# Sheet1.net
KiCad netlist of a schematic drawn in Altium Designer
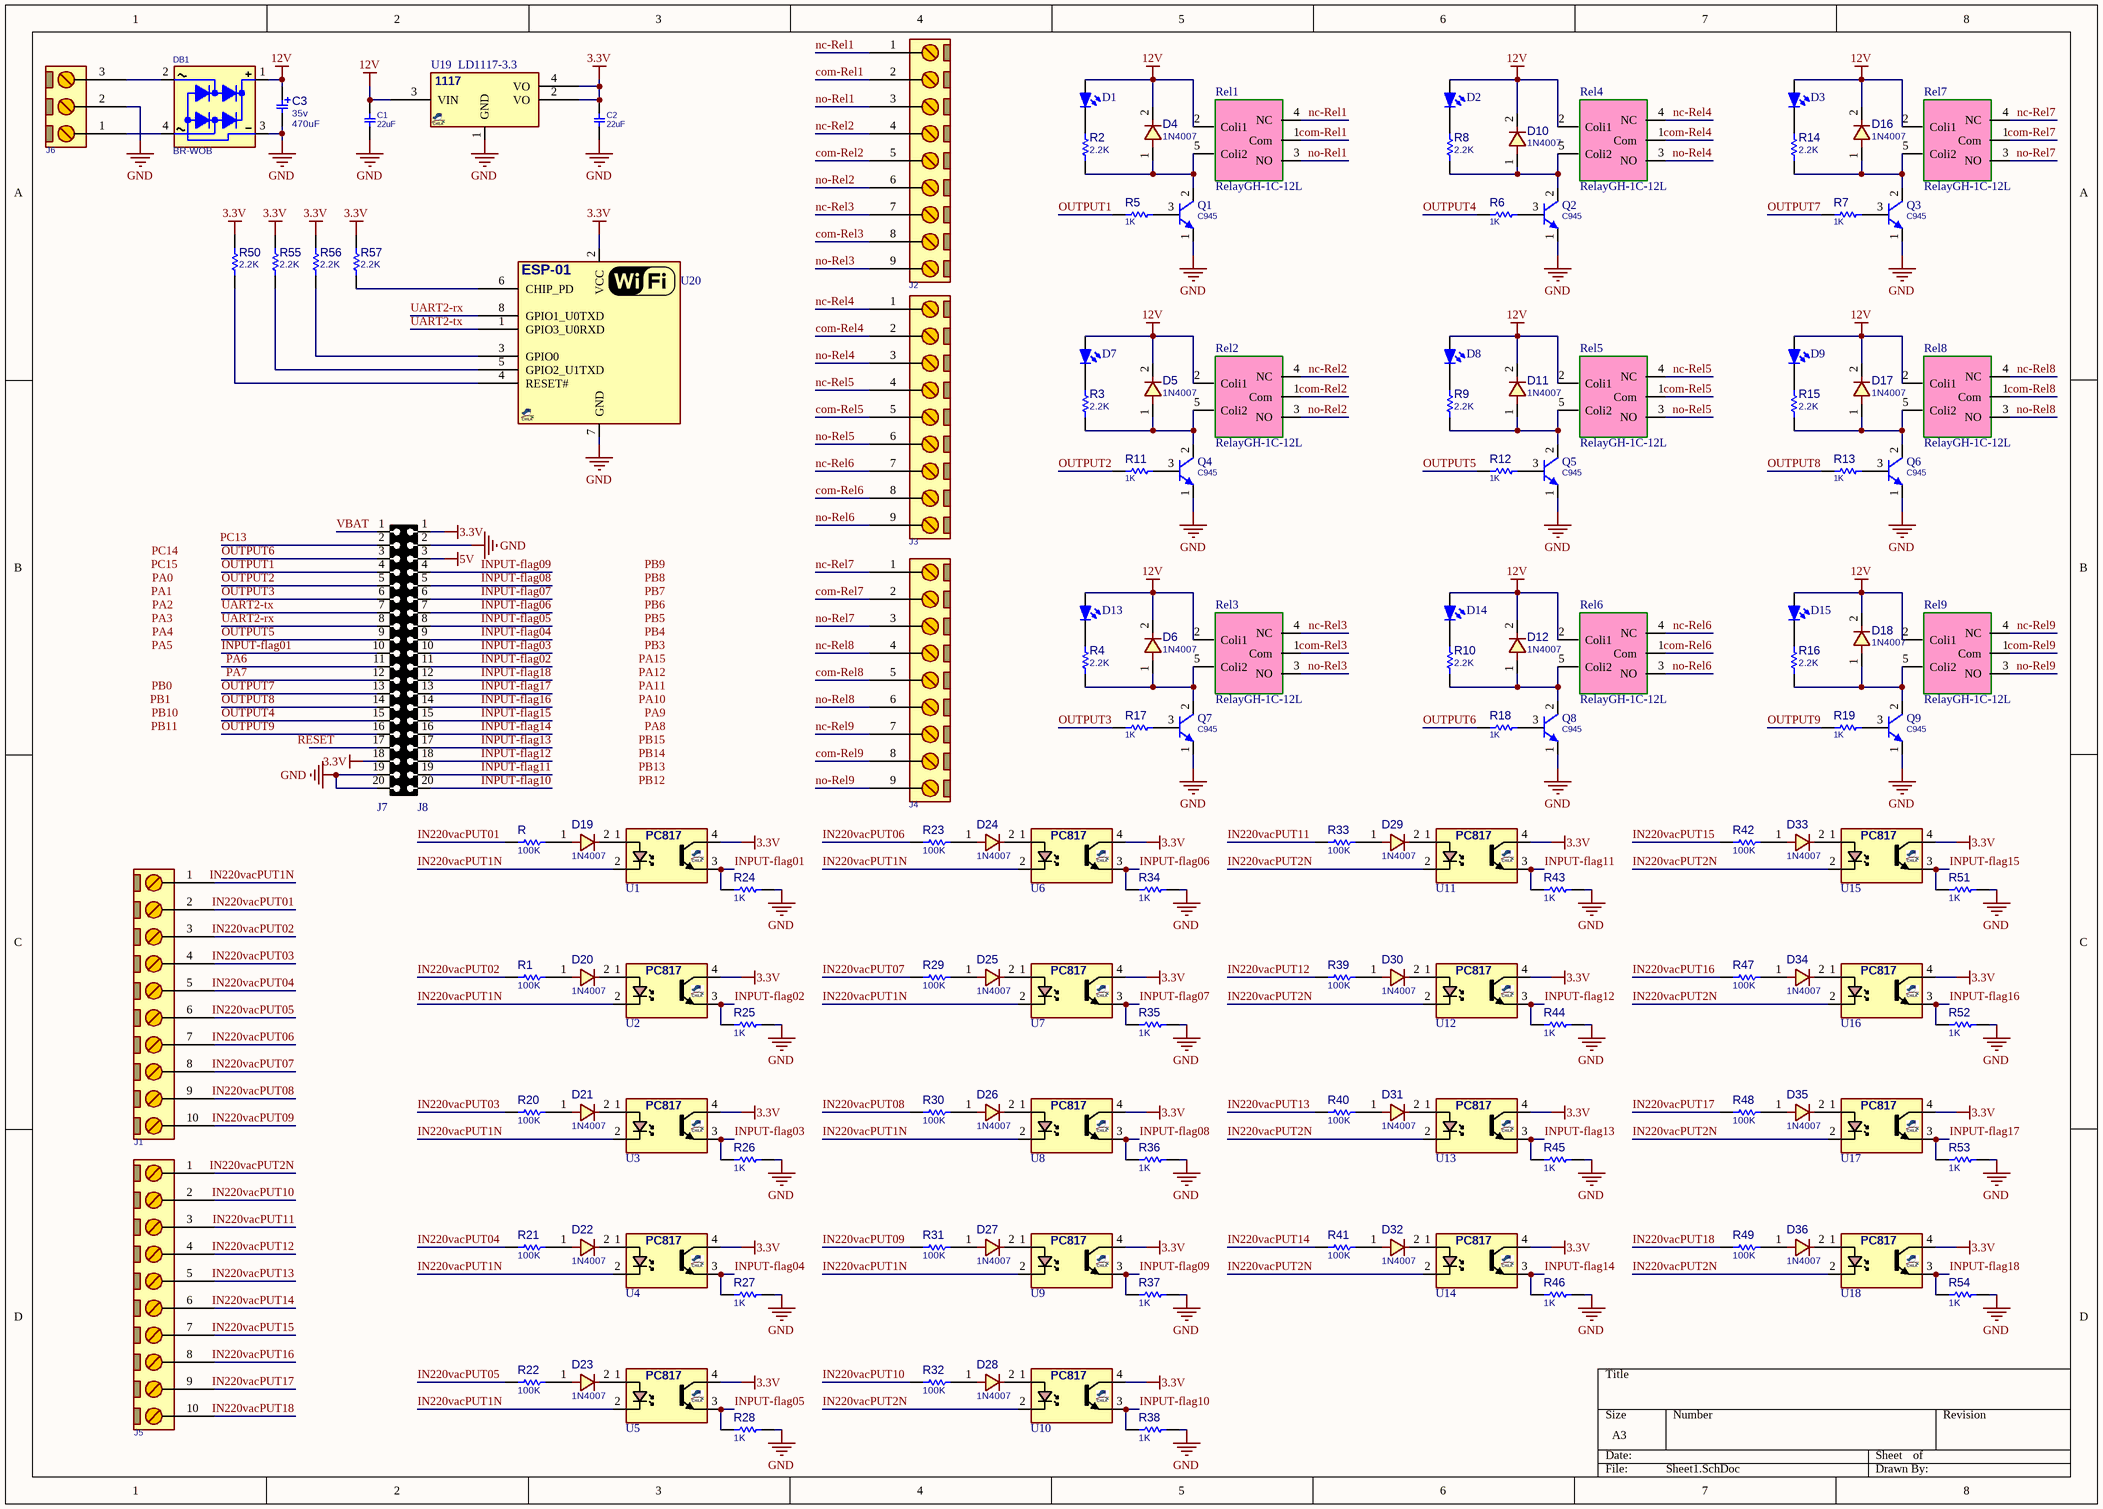
[diagram p0: Sheet1.SchDoc]

(export (version "E")
  (design (tool "Eeschema 10.0.6"))
  (components
    (comp (ref "C1")
      (value "22uF")
      (footprint "C0805")
      (description "CAP, MLCC, X5R 10uF 10% 25V 0805")
      (fields (field (name "MANF_P#") "TMK212BBJ106MG") (field (name "MANF") "Taiyo Yuden"))
      (libsource (lib "mlcc_smd_passive") (part "CAP_SMD_MLCC_10u25V"))
    )
    (comp (ref "C2")
      (value "22uF")
      (footprint "C0805")
      (description "CAP, MLCC, X5R 10uF 10% 25V 0805")
      (fields (field (name "MANF_P#") "TMK212BBJ106MG") (field (name "MANF") "Taiyo Yuden"))
      (libsource (lib "mlcc_smd_passive") (part "CAP_SMD_MLCC_10u25V"))
    )
    (comp (ref "C3")
      (value "470uF")
      (footprint "C_EL_10X16")
      (description "CAP, THD, ELEC,")
      (fields
        (field (name "MANF_P#") "MANF_PART#")
        (field (name "MANF") "MANF")
        (field (name "PARAM2") "35v")
      )
      (libsource (lib "passive_thd") (part "CAP_THD_EL_470uF_35v"))
    )
    (comp (ref "D1")
      (value "~")
      (footprint "0805 LED")
      (description "Led")
      (fields (field (name "PUBLISHER") "Altium Limited"))
      (libsource (lib "Sajad_Altium_Library") (part "LED"))
    )
    (comp (ref "D2")
      (value "~")
      (footprint "0805 LED")
      (description "Led")
      (fields (field (name "PUBLISHER") "Altium Limited"))
      (libsource (lib "Sajad_Altium_Library") (part "LED"))
    )
    (comp (ref "D3")
      (value "~")
      (footprint "0805 LED")
      (description "Led")
      (fields (field (name "PUBLISHER") "Altium Limited"))
      (libsource (lib "Sajad_Altium_Library") (part "LED"))
    )
    (comp (ref "D4")
      (value "1N4007")
      (footprint "D_SMA")
      (description "DIODE, GENERAL PURPOSE, 1000V/1A")
      (fields (field (name "MANF") "Kingtronics") (field (name "MANF_P#") "M7"))
      (libsource (lib "diode") (part "DIODE_SMD_1N4007"))
    )
    (comp (ref "D5")
      (value "1N4007")
      (footprint "D_SMA")
      (description "DIODE, GENERAL PURPOSE, 1000V/1A")
      (fields (field (name "MANF") "Kingtronics") (field (name "MANF_P#") "M7"))
      (libsource (lib "diode") (part "DIODE_SMD_1N4007"))
    )
    (comp (ref "D6")
      (value "1N4007")
      (footprint "D_SMA")
      (description "DIODE, GENERAL PURPOSE, 1000V/1A")
      (fields (field (name "MANF") "Kingtronics") (field (name "MANF_P#") "M7"))
      (libsource (lib "diode") (part "DIODE_SMD_1N4007"))
    )
    (comp (ref "D7")
      (value "~")
      (footprint "0805 LED")
      (description "Led")
      (fields (field (name "PUBLISHER") "Altium Limited"))
      (libsource (lib "Sajad_Altium_Library") (part "LED"))
    )
    (comp (ref "D8")
      (value "~")
      (footprint "0805 LED")
      (description "Led")
      (fields (field (name "PUBLISHER") "Altium Limited"))
      (libsource (lib "Sajad_Altium_Library") (part "LED"))
    )
    (comp (ref "D9")
      (value "~")
      (footprint "0805 LED")
      (description "Led")
      (fields (field (name "PUBLISHER") "Altium Limited"))
      (libsource (lib "Sajad_Altium_Library") (part "LED"))
    )
    (comp (ref "D10")
      (value "1N4007")
      (footprint "D_SMA")
      (description "DIODE, GENERAL PURPOSE, 1000V/1A")
      (fields (field (name "MANF") "Kingtronics") (field (name "MANF_P#") "M7"))
      (libsource (lib "diode") (part "DIODE_SMD_1N4007"))
    )
    (comp (ref "D11")
      (value "1N4007")
      (footprint "D_SMA")
      (description "DIODE, GENERAL PURPOSE, 1000V/1A")
      (fields (field (name "MANF") "Kingtronics") (field (name "MANF_P#") "M7"))
      (libsource (lib "diode") (part "DIODE_SMD_1N4007"))
    )
    (comp (ref "D12")
      (value "1N4007")
      (footprint "D_SMA")
      (description "DIODE, GENERAL PURPOSE, 1000V/1A")
      (fields (field (name "MANF") "Kingtronics") (field (name "MANF_P#") "M7"))
      (libsource (lib "diode") (part "DIODE_SMD_1N4007"))
    )
    (comp (ref "D13")
      (value "~")
      (footprint "0805 LED")
      (description "Led")
      (fields (field (name "PUBLISHER") "Altium Limited"))
      (libsource (lib "Sajad_Altium_Library") (part "LED"))
    )
    (comp (ref "D14")
      (value "~")
      (footprint "0805 LED")
      (description "Led")
      (fields (field (name "PUBLISHER") "Altium Limited"))
      (libsource (lib "Sajad_Altium_Library") (part "LED"))
    )
    (comp (ref "D15")
      (value "~")
      (footprint "0805 LED")
      (description "Led")
      (fields (field (name "PUBLISHER") "Altium Limited"))
      (libsource (lib "Sajad_Altium_Library") (part "LED"))
    )
    (comp (ref "D16")
      (value "1N4007")
      (footprint "D_SMA")
      (description "DIODE, GENERAL PURPOSE, 1000V/1A")
      (fields (field (name "MANF") "Kingtronics") (field (name "MANF_P#") "M7"))
      (libsource (lib "diode") (part "DIODE_SMD_1N4007"))
    )
    (comp (ref "D17")
      (value "1N4007")
      (footprint "D_SMA")
      (description "DIODE, GENERAL PURPOSE, 1000V/1A")
      (fields (field (name "MANF") "Kingtronics") (field (name "MANF_P#") "M7"))
      (libsource (lib "diode") (part "DIODE_SMD_1N4007"))
    )
    (comp (ref "D18")
      (value "1N4007")
      (footprint "D_SMA")
      (description "DIODE, GENERAL PURPOSE, 1000V/1A")
      (fields (field (name "MANF") "Kingtronics") (field (name "MANF_P#") "M7"))
      (libsource (lib "diode") (part "DIODE_SMD_1N4007"))
    )
    (comp (ref "D19")
      (value "1N4007")
      (footprint "D_SMA")
      (description "DIODE, GENERAL PURPOSE, 1000V/1A")
      (fields (field (name "MANF") "Kingtronics") (field (name "MANF_P#") "M7"))
      (libsource (lib "diode") (part "DIODE_SMD_1N4007"))
    )
    (comp (ref "D20")
      (value "1N4007")
      (footprint "D_SMA")
      (description "DIODE, GENERAL PURPOSE, 1000V/1A")
      (fields (field (name "MANF") "Kingtronics") (field (name "MANF_P#") "M7"))
      (libsource (lib "diode") (part "DIODE_SMD_1N4007"))
    )
    (comp (ref "D21")
      (value "1N4007")
      (footprint "D_SMA")
      (description "DIODE, GENERAL PURPOSE, 1000V/1A")
      (fields (field (name "MANF") "Kingtronics") (field (name "MANF_P#") "M7"))
      (libsource (lib "diode") (part "DIODE_SMD_1N4007"))
    )
    (comp (ref "D22")
      (value "1N4007")
      (footprint "D_SMA")
      (description "DIODE, GENERAL PURPOSE, 1000V/1A")
      (fields (field (name "MANF") "Kingtronics") (field (name "MANF_P#") "M7"))
      (libsource (lib "diode") (part "DIODE_SMD_1N4007"))
    )
    (comp (ref "D23")
      (value "1N4007")
      (footprint "D_SMA")
      (description "DIODE, GENERAL PURPOSE, 1000V/1A")
      (fields (field (name "MANF") "Kingtronics") (field (name "MANF_P#") "M7"))
      (libsource (lib "diode") (part "DIODE_SMD_1N4007"))
    )
    (comp (ref "D24")
      (value "1N4007")
      (footprint "D_SMA")
      (description "DIODE, GENERAL PURPOSE, 1000V/1A")
      (fields (field (name "MANF") "Kingtronics") (field (name "MANF_P#") "M7"))
      (libsource (lib "diode") (part "DIODE_SMD_1N4007"))
    )
    (comp (ref "D25")
      (value "1N4007")
      (footprint "D_SMA")
      (description "DIODE, GENERAL PURPOSE, 1000V/1A")
      (fields (field (name "MANF") "Kingtronics") (field (name "MANF_P#") "M7"))
      (libsource (lib "diode") (part "DIODE_SMD_1N4007"))
    )
    (comp (ref "D26")
      (value "1N4007")
      (footprint "D_SMA")
      (description "DIODE, GENERAL PURPOSE, 1000V/1A")
      (fields (field (name "MANF") "Kingtronics") (field (name "MANF_P#") "M7"))
      (libsource (lib "diode") (part "DIODE_SMD_1N4007"))
    )
    (comp (ref "D27")
      (value "1N4007")
      (footprint "D_SMA")
      (description "DIODE, GENERAL PURPOSE, 1000V/1A")
      (fields (field (name "MANF") "Kingtronics") (field (name "MANF_P#") "M7"))
      (libsource (lib "diode") (part "DIODE_SMD_1N4007"))
    )
    (comp (ref "D28")
      (value "1N4007")
      (footprint "D_SMA")
      (description "DIODE, GENERAL PURPOSE, 1000V/1A")
      (fields (field (name "MANF") "Kingtronics") (field (name "MANF_P#") "M7"))
      (libsource (lib "diode") (part "DIODE_SMD_1N4007"))
    )
    (comp (ref "D29")
      (value "1N4007")
      (footprint "D_SMA")
      (description "DIODE, GENERAL PURPOSE, 1000V/1A")
      (fields (field (name "MANF") "Kingtronics") (field (name "MANF_P#") "M7"))
      (libsource (lib "diode") (part "DIODE_SMD_1N4007"))
    )
    (comp (ref "D30")
      (value "1N4007")
      (footprint "D_SMA")
      (description "DIODE, GENERAL PURPOSE, 1000V/1A")
      (fields (field (name "MANF") "Kingtronics") (field (name "MANF_P#") "M7"))
      (libsource (lib "diode") (part "DIODE_SMD_1N4007"))
    )
    (comp (ref "D31")
      (value "1N4007")
      (footprint "D_SMA")
      (description "DIODE, GENERAL PURPOSE, 1000V/1A")
      (fields (field (name "MANF") "Kingtronics") (field (name "MANF_P#") "M7"))
      (libsource (lib "diode") (part "DIODE_SMD_1N4007"))
    )
    (comp (ref "D32")
      (value "1N4007")
      (footprint "D_SMA")
      (description "DIODE, GENERAL PURPOSE, 1000V/1A")
      (fields (field (name "MANF") "Kingtronics") (field (name "MANF_P#") "M7"))
      (libsource (lib "diode") (part "DIODE_SMD_1N4007"))
    )
    (comp (ref "D33")
      (value "1N4007")
      (footprint "D_SMA")
      (description "DIODE, GENERAL PURPOSE, 1000V/1A")
      (fields (field (name "MANF") "Kingtronics") (field (name "MANF_P#") "M7"))
      (libsource (lib "diode") (part "DIODE_SMD_1N4007"))
    )
    (comp (ref "D34")
      (value "1N4007")
      (footprint "D_SMA")
      (description "DIODE, GENERAL PURPOSE, 1000V/1A")
      (fields (field (name "MANF") "Kingtronics") (field (name "MANF_P#") "M7"))
      (libsource (lib "diode") (part "DIODE_SMD_1N4007"))
    )
    (comp (ref "D35")
      (value "1N4007")
      (footprint "D_SMA")
      (description "DIODE, GENERAL PURPOSE, 1000V/1A")
      (fields (field (name "MANF") "Kingtronics") (field (name "MANF_P#") "M7"))
      (libsource (lib "diode") (part "DIODE_SMD_1N4007"))
    )
    (comp (ref "D36")
      (value "1N4007")
      (footprint "D_SMA")
      (description "DIODE, GENERAL PURPOSE, 1000V/1A")
      (fields (field (name "MANF") "Kingtronics") (field (name "MANF_P#") "M7"))
      (libsource (lib "diode") (part "DIODE_SMD_1N4007"))
    )
    (comp (ref "DB1")
      (value "BR-WOB")
      (footprint "DBRG_C10")
      (description "DIODE, BRIDGE,")
      (libsource (lib "diode") (part "DIODE_THD_BRIDGE_WO"))
    )
    (comp (ref "J1")
      (value "CONN_TB10")
      (footprint "MSTB_10")
      (description "CONN, PHOENIX MSTB, 5-G, 5.08mm pitch")
      (libsource (lib "conn_terminalB") (part "CONN_MSTB_10"))
    )
    (comp (ref "J2")
      (value "CONN_TB9")
      (footprint "MSTB_9")
      (description "CONN, PHOENIX MSTB, 5-G, 5.08mm pitch")
      (libsource (lib "conn_terminalB") (part "CONN_MSTB_9"))
    )
    (comp (ref "J3")
      (value "CONN_TB9")
      (footprint "MSTB_9")
      (description "CONN, PHOENIX MSTB, 5-G, 5.08mm pitch")
      (libsource (lib "conn_terminalB") (part "CONN_MSTB_9"))
    )
    (comp (ref "J4")
      (value "CONN_TB9")
      (footprint "MSTB_9")
      (description "CONN, PHOENIX MSTB, 5-G, 5.08mm pitch")
      (libsource (lib "conn_terminalB") (part "CONN_MSTB_9"))
    )
    (comp (ref "J5")
      (value "CONN_TB10")
      (footprint "MSTB_10")
      (description "CONN, PHOENIX MSTB, 5-G, 5.08mm pitch")
      (libsource (lib "conn_terminalB") (part "CONN_MSTB_10"))
    )
    (comp (ref "J6")
      (value "CONN_TB3")
      (footprint "MSTB_3")
      (description "CONN, PHOENIX MSTB, 5-G, 5.08mm pitch")
      (libsource (lib "conn_terminalB") (part "CONN_MSTB_3"))
    )
    (comp (ref "J7")
      (value "HDRF20")
      (footprint "HDR_F_1X20")
      (description "CONN, HEADER, Female, pitch: 2.54mm, 20POS")
      (libsource (lib "conn_header_2.54_st") (part "HDR_F_1X20"))
    )
    (comp (ref "J8")
      (value "HDRF20")
      (footprint "HDR_F_1X20")
      (description "CONN, HEADER, Female, pitch: 2.54mm, 20POS")
      (libsource (lib "conn_header_2.54_st") (part "HDR_F_1X20"))
    )
    (comp (ref "Q1")
      (value "C945")
      (footprint "TO92_3")
      (description "BJT, NPN, 50v, 0.15A, THD, TO92, BC945")
      (fields (field (name "MANF_P#") "C945, 2SC945, BC945"))
      (libsource (lib "transistor_bjt") (part "NPN_C945_TO92"))
    )
    (comp (ref "Q2")
      (value "C945")
      (footprint "TO92_3")
      (description "BJT, NPN, 50v, 0.15A, THD, TO92, BC945")
      (fields (field (name "MANF_P#") "C945, 2SC945, BC945"))
      (libsource (lib "transistor_bjt") (part "NPN_C945_TO92"))
    )
    (comp (ref "Q3")
      (value "C945")
      (footprint "TO92_3")
      (description "BJT, NPN, 50v, 0.15A, THD, TO92, BC945")
      (fields (field (name "MANF_P#") "C945, 2SC945, BC945"))
      (libsource (lib "transistor_bjt") (part "NPN_C945_TO92"))
    )
    (comp (ref "Q4")
      (value "C945")
      (footprint "TO92_3")
      (description "BJT, NPN, 50v, 0.15A, THD, TO92, BC945")
      (fields (field (name "MANF_P#") "C945, 2SC945, BC945"))
      (libsource (lib "transistor_bjt") (part "NPN_C945_TO92"))
    )
    (comp (ref "Q5")
      (value "C945")
      (footprint "TO92_3")
      (description "BJT, NPN, 50v, 0.15A, THD, TO92, BC945")
      (fields (field (name "MANF_P#") "C945, 2SC945, BC945"))
      (libsource (lib "transistor_bjt") (part "NPN_C945_TO92"))
    )
    (comp (ref "Q6")
      (value "C945")
      (footprint "TO92_3")
      (description "BJT, NPN, 50v, 0.15A, THD, TO92, BC945")
      (fields (field (name "MANF_P#") "C945, 2SC945, BC945"))
      (libsource (lib "transistor_bjt") (part "NPN_C945_TO92"))
    )
    (comp (ref "Q7")
      (value "C945")
      (footprint "TO92_3")
      (description "BJT, NPN, 50v, 0.15A, THD, TO92, BC945")
      (fields (field (name "MANF_P#") "C945, 2SC945, BC945"))
      (libsource (lib "transistor_bjt") (part "NPN_C945_TO92"))
    )
    (comp (ref "Q8")
      (value "C945")
      (footprint "TO92_3")
      (description "BJT, NPN, 50v, 0.15A, THD, TO92, BC945")
      (fields (field (name "MANF_P#") "C945, 2SC945, BC945"))
      (libsource (lib "transistor_bjt") (part "NPN_C945_TO92"))
    )
    (comp (ref "Q9")
      (value "C945")
      (footprint "TO92_3")
      (description "BJT, NPN, 50v, 0.15A, THD, TO92, BC945")
      (fields (field (name "MANF_P#") "C945, 2SC945, BC945"))
      (libsource (lib "transistor_bjt") (part "NPN_C945_TO92"))
    )
    (comp (ref "R")
      (value "100K")
      (footprint "R0805")
      (description "RESISTOR, SMD")
      (libsource (lib "passive_smd") (part "RES_SMD_0805"))
    )
    (comp (ref "R1")
      (value "100K")
      (footprint "R0805")
      (description "RESISTOR, SMD")
      (libsource (lib "passive_smd") (part "RES_SMD"))
    )
    (comp (ref "R2")
      (value "2.2K")
      (footprint "R0805")
      (description "RESISTOR, SMD")
      (libsource (lib "passive_smd") (part "RES_SMD"))
    )
    (comp (ref "R3")
      (value "2.2K")
      (footprint "R0805")
      (description "RESISTOR, SMD")
      (libsource (lib "passive_smd") (part "RES_SMD"))
    )
    (comp (ref "R4")
      (value "2.2K")
      (footprint "R0805")
      (description "RESISTOR, SMD")
      (libsource (lib "passive_smd") (part "RES_SMD"))
    )
    (comp (ref "R5")
      (value "1K")
      (footprint "R025W_AX04")
      (description "RESISTOR, THD")
      (fields (field (name "MANF_P#") "RK73H1ETTP4701F") (field (name "MANF") "KOA SPEER"))
      (libsource (lib "passive_thd") (part "RES_THD"))
    )
    (comp (ref "R6")
      (value "1K")
      (footprint "R025W_AX04")
      (description "RESISTOR, THD")
      (fields (field (name "MANF_P#") "RK73H1ETTP4701F") (field (name "MANF") "KOA SPEER"))
      (libsource (lib "passive_thd") (part "RES_THD"))
    )
    (comp (ref "R7")
      (value "1K")
      (footprint "R025W_AX04")
      (description "RESISTOR, THD")
      (fields (field (name "MANF_P#") "RK73H1ETTP4701F") (field (name "MANF") "KOA SPEER"))
      (libsource (lib "passive_thd") (part "RES_THD"))
    )
    (comp (ref "R8")
      (value "2.2K")
      (footprint "R0805")
      (description "RESISTOR, SMD")
      (libsource (lib "passive_smd") (part "RES_SMD"))
    )
    (comp (ref "R9")
      (value "2.2K")
      (footprint "R0805")
      (description "RESISTOR, SMD")
      (libsource (lib "passive_smd") (part "RES_SMD"))
    )
    (comp (ref "R10")
      (value "2.2K")
      (footprint "R0805")
      (description "RESISTOR, SMD")
      (libsource (lib "passive_smd") (part "RES_SMD"))
    )
    (comp (ref "R11")
      (value "1K")
      (footprint "R025W_AX04")
      (description "RESISTOR, THD")
      (fields (field (name "MANF_P#") "RK73H1ETTP4701F") (field (name "MANF") "KOA SPEER"))
      (libsource (lib "passive_thd") (part "RES_THD"))
    )
    (comp (ref "R12")
      (value "1K")
      (footprint "R025W_AX04")
      (description "RESISTOR, THD")
      (fields (field (name "MANF_P#") "RK73H1ETTP4701F") (field (name "MANF") "KOA SPEER"))
      (libsource (lib "passive_thd") (part "RES_THD"))
    )
    (comp (ref "R13")
      (value "1K")
      (footprint "R025W_AX04")
      (description "RESISTOR, THD")
      (fields (field (name "MANF_P#") "RK73H1ETTP4701F") (field (name "MANF") "KOA SPEER"))
      (libsource (lib "passive_thd") (part "RES_THD"))
    )
    (comp (ref "R14")
      (value "2.2K")
      (footprint "R0805")
      (description "RESISTOR, SMD")
      (libsource (lib "passive_smd") (part "RES_SMD"))
    )
    (comp (ref "R15")
      (value "2.2K")
      (footprint "R0805")
      (description "RESISTOR, SMD")
      (libsource (lib "passive_smd") (part "RES_SMD"))
    )
    (comp (ref "R16")
      (value "2.2K")
      (footprint "R0805")
      (description "RESISTOR, SMD")
      (libsource (lib "passive_smd") (part "RES_SMD"))
    )
    (comp (ref "R17")
      (value "1K")
      (footprint "R025W_AX04")
      (description "RESISTOR, THD")
      (fields (field (name "MANF_P#") "RK73H1ETTP4701F") (field (name "MANF") "KOA SPEER"))
      (libsource (lib "passive_thd") (part "RES_THD"))
    )
    (comp (ref "R18")
      (value "1K")
      (footprint "R025W_AX04")
      (description "RESISTOR, THD")
      (fields (field (name "MANF_P#") "RK73H1ETTP4701F") (field (name "MANF") "KOA SPEER"))
      (libsource (lib "passive_thd") (part "RES_THD"))
    )
    (comp (ref "R19")
      (value "1K")
      (footprint "R025W_AX04")
      (description "RESISTOR, THD")
      (fields (field (name "MANF_P#") "RK73H1ETTP4701F") (field (name "MANF") "KOA SPEER"))
      (libsource (lib "passive_thd") (part "RES_THD"))
    )
    (comp (ref "R20")
      (value "100K")
      (footprint "R0805")
      (description "RESISTOR, SMD")
      (libsource (lib "passive_smd") (part "RES_SMD"))
    )
    (comp (ref "R21")
      (value "100K")
      (footprint "R0805")
      (description "RESISTOR, SMD")
      (libsource (lib "passive_smd") (part "RES_SMD"))
    )
    (comp (ref "R22")
      (value "100K")
      (footprint "R0805")
      (description "RESISTOR, SMD")
      (libsource (lib "passive_smd") (part "RES_SMD"))
    )
    (comp (ref "R23")
      (value "100K")
      (footprint "R0805")
      (description "RESISTOR, SMD")
      (libsource (lib "passive_smd") (part "RES_SMD"))
    )
    (comp (ref "R24")
      (value "1K")
      (footprint "R0805")
      (description "RESISTOR, SMD")
      (libsource (lib "passive_smd") (part "RES_SMD"))
    )
    (comp (ref "R25")
      (value "1K")
      (footprint "R0805")
      (description "RESISTOR, SMD")
      (libsource (lib "passive_smd") (part "RES_SMD"))
    )
    (comp (ref "R26")
      (value "1K")
      (footprint "R0805")
      (description "RESISTOR, SMD")
      (libsource (lib "passive_smd") (part "RES_SMD"))
    )
    (comp (ref "R27")
      (value "1K")
      (footprint "R0805")
      (description "RESISTOR, SMD")
      (libsource (lib "passive_smd") (part "RES_SMD"))
    )
    (comp (ref "R28")
      (value "1K")
      (footprint "R0805")
      (description "RESISTOR, SMD")
      (libsource (lib "passive_smd") (part "RES_SMD"))
    )
    (comp (ref "R29")
      (value "100K")
      (footprint "R0805")
      (description "RESISTOR, SMD")
      (libsource (lib "passive_smd") (part "RES_SMD"))
    )
    (comp (ref "R30")
      (value "100K")
      (footprint "R0805")
      (description "RESISTOR, SMD")
      (libsource (lib "passive_smd") (part "RES_SMD"))
    )
    (comp (ref "R31")
      (value "100K")
      (footprint "R0805")
      (description "RESISTOR, SMD")
      (libsource (lib "passive_smd") (part "RES_SMD"))
    )
    (comp (ref "R32")
      (value "100K")
      (footprint "R0805")
      (description "RESISTOR, SMD")
      (libsource (lib "passive_smd") (part "RES_SMD"))
    )
    (comp (ref "R33")
      (value "100K")
      (footprint "R0805")
      (description "RESISTOR, SMD")
      (libsource (lib "passive_smd") (part "RES_SMD"))
    )
    (comp (ref "R34")
      (value "1K")
      (footprint "R0805")
      (description "RESISTOR, SMD")
      (libsource (lib "passive_smd") (part "RES_SMD"))
    )
    (comp (ref "R35")
      (value "1K")
      (footprint "R0805")
      (description "RESISTOR, SMD")
      (libsource (lib "passive_smd") (part "RES_SMD"))
    )
    (comp (ref "R36")
      (value "1K")
      (footprint "R0805")
      (description "RESISTOR, SMD")
      (libsource (lib "passive_smd") (part "RES_SMD"))
    )
    (comp (ref "R37")
      (value "1K")
      (footprint "R0805")
      (description "RESISTOR, SMD")
      (libsource (lib "passive_smd") (part "RES_SMD"))
    )
    (comp (ref "R38")
      (value "1K")
      (footprint "R0805")
      (description "RESISTOR, SMD")
      (libsource (lib "passive_smd") (part "RES_SMD"))
    )
    (comp (ref "R39")
      (value "100K")
      (footprint "R0805")
      (description "RESISTOR, SMD")
      (libsource (lib "passive_smd") (part "RES_SMD"))
    )
    (comp (ref "R40")
      (value "100K")
      (footprint "R0805")
      (description "RESISTOR, SMD")
      (libsource (lib "passive_smd") (part "RES_SMD"))
    )
    (comp (ref "R41")
      (value "100K")
      (footprint "R0805")
      (description "RESISTOR, SMD")
      (libsource (lib "passive_smd") (part "RES_SMD"))
    )
    (comp (ref "R42")
      (value "100K")
      (footprint "R0805")
      (description "RESISTOR, SMD")
      (libsource (lib "passive_smd") (part "RES_SMD"))
    )
    (comp (ref "R43")
      (value "1K")
      (footprint "R0805")
      (description "RESISTOR, SMD")
      (libsource (lib "passive_smd") (part "RES_SMD"))
    )
    (comp (ref "R44")
      (value "1K")
      (footprint "R0805")
      (description "RESISTOR, SMD")
      (libsource (lib "passive_smd") (part "RES_SMD"))
    )
    (comp (ref "R45")
      (value "1K")
      (footprint "R0805")
      (description "RESISTOR, SMD")
      (libsource (lib "passive_smd") (part "RES_SMD"))
    )
    (comp (ref "R46")
      (value "1K")
      (footprint "R0805")
      (description "RESISTOR, SMD")
      (libsource (lib "passive_smd") (part "RES_SMD"))
    )
    (comp (ref "R47")
      (value "100K")
      (footprint "R0805")
      (description "RESISTOR, SMD")
      (libsource (lib "passive_smd") (part "RES_SMD"))
    )
    (comp (ref "R48")
      (value "100K")
      (footprint "R0805")
      (description "RESISTOR, SMD")
      (libsource (lib "passive_smd") (part "RES_SMD"))
    )
    (comp (ref "R49")
      (value "100K")
      (footprint "R0805")
      (description "RESISTOR, SMD")
      (libsource (lib "passive_smd") (part "RES_SMD"))
    )
    (comp (ref "R50")
      (value "2.2K")
      (footprint "R0805")
      (description "RESISTOR, SMD")
      (libsource (lib "passive_smd") (part "RES_SMD"))
    )
    (comp (ref "R51")
      (value "1K")
      (footprint "R0805")
      (description "RESISTOR, SMD")
      (libsource (lib "passive_smd") (part "RES_SMD"))
    )
    (comp (ref "R52")
      (value "1K")
      (footprint "R0805")
      (description "RESISTOR, SMD")
      (libsource (lib "passive_smd") (part "RES_SMD"))
    )
    (comp (ref "R53")
      (value "1K")
      (footprint "R0805")
      (description "RESISTOR, SMD")
      (libsource (lib "passive_smd") (part "RES_SMD"))
    )
    (comp (ref "R54")
      (value "1K")
      (footprint "R0805")
      (description "RESISTOR, SMD")
      (libsource (lib "passive_smd") (part "RES_SMD"))
    )
    (comp (ref "R55")
      (value "2.2K")
      (footprint "R0805")
      (description "RESISTOR, SMD")
      (libsource (lib "passive_smd") (part "RES_SMD"))
    )
    (comp (ref "R56")
      (value "2.2K")
      (footprint "R0805")
      (description "RESISTOR, SMD")
      (libsource (lib "passive_smd") (part "RES_SMD"))
    )
    (comp (ref "R57")
      (value "2.2K")
      (footprint "R0805")
      (description "RESISTOR, SMD")
      (libsource (lib "passive_smd") (part "RES_SMD"))
    )
    (comp (ref "Rel1")
      (value "RelayGH-1C-12L")
      (footprint "GH-1C-12L")
      (description "HJR-3FF-12VDC-S-Z")
      (libsource (lib "Sajad_Altium_Library") (part "RelayGH-1C-12L"))
    )
    (comp (ref "Rel2")
      (value "RelayGH-1C-12L")
      (footprint "GH-1C-12L")
      (description "HJR-3FF-12VDC-S-Z")
      (libsource (lib "Sajad_Altium_Library") (part "RelayGH-1C-12L"))
    )
    (comp (ref "Rel3")
      (value "RelayGH-1C-12L")
      (footprint "GH-1C-12L")
      (description "HJR-3FF-12VDC-S-Z")
      (libsource (lib "Sajad_Altium_Library") (part "RelayGH-1C-12L"))
    )
    (comp (ref "Rel4")
      (value "RelayGH-1C-12L")
      (footprint "GH-1C-12L")
      (description "HJR-3FF-12VDC-S-Z")
      (libsource (lib "Sajad_Altium_Library") (part "RelayGH-1C-12L"))
    )
    (comp (ref "Rel5")
      (value "RelayGH-1C-12L")
      (footprint "GH-1C-12L")
      (description "HJR-3FF-12VDC-S-Z")
      (libsource (lib "Sajad_Altium_Library") (part "RelayGH-1C-12L"))
    )
    (comp (ref "Rel6")
      (value "RelayGH-1C-12L")
      (footprint "GH-1C-12L")
      (description "HJR-3FF-12VDC-S-Z")
      (libsource (lib "Sajad_Altium_Library") (part "RelayGH-1C-12L"))
    )
    (comp (ref "Rel7")
      (value "RelayGH-1C-12L")
      (footprint "GH-1C-12L")
      (description "HJR-3FF-12VDC-S-Z")
      (libsource (lib "Sajad_Altium_Library") (part "RelayGH-1C-12L"))
    )
    (comp (ref "Rel8")
      (value "RelayGH-1C-12L")
      (footprint "GH-1C-12L")
      (description "HJR-3FF-12VDC-S-Z")
      (libsource (lib "Sajad_Altium_Library") (part "RelayGH-1C-12L"))
    )
    (comp (ref "Rel9")
      (value "RelayGH-1C-12L")
      (footprint "GH-1C-12L")
      (description "HJR-3FF-12VDC-S-Z")
      (libsource (lib "Sajad_Altium_Library") (part "RelayGH-1C-12L"))
    )
    (comp (ref "U1")
      (value "PC817")
      (footprint "DIP_4")
      (description "OPTOCOUPLER, TRANSISTOR, 4PIN")
      (fields (field (name "MANF") "SHARP"))
      (libsource (lib "optocoupler") (part "OPTC_TR4P_PC817"))
    )
    (comp (ref "U2")
      (value "PC817")
      (footprint "DIP_4")
      (description "OPTOCOUPLER, TRANSISTOR, 4PIN")
      (fields (field (name "MANF") "SHARP"))
      (libsource (lib "optocoupler") (part "OPTC_TR4P_PC817"))
    )
    (comp (ref "U3")
      (value "PC817")
      (footprint "DIP_4")
      (description "OPTOCOUPLER, TRANSISTOR, 4PIN")
      (fields (field (name "MANF") "SHARP"))
      (libsource (lib "optocoupler") (part "OPTC_TR4P_PC817"))
    )
    (comp (ref "U4")
      (value "PC817")
      (footprint "DIP_4")
      (description "OPTOCOUPLER, TRANSISTOR, 4PIN")
      (fields (field (name "MANF") "SHARP"))
      (libsource (lib "optocoupler") (part "OPTC_TR4P_PC817"))
    )
    (comp (ref "U5")
      (value "PC817")
      (footprint "DIP_4")
      (description "OPTOCOUPLER, TRANSISTOR, 4PIN")
      (fields (field (name "MANF") "SHARP"))
      (libsource (lib "optocoupler") (part "OPTC_TR4P_PC817"))
    )
    (comp (ref "U6")
      (value "PC817")
      (footprint "DIP_4")
      (description "OPTOCOUPLER, TRANSISTOR, 4PIN")
      (fields (field (name "MANF") "SHARP"))
      (libsource (lib "optocoupler") (part "OPTC_TR4P_PC817"))
    )
    (comp (ref "U7")
      (value "PC817")
      (footprint "DIP_4")
      (description "OPTOCOUPLER, TRANSISTOR, 4PIN")
      (fields (field (name "MANF") "SHARP"))
      (libsource (lib "optocoupler") (part "OPTC_TR4P_PC817"))
    )
    (comp (ref "U8")
      (value "PC817")
      (footprint "DIP_4")
      (description "OPTOCOUPLER, TRANSISTOR, 4PIN")
      (fields (field (name "MANF") "SHARP"))
      (libsource (lib "optocoupler") (part "OPTC_TR4P_PC817"))
    )
    (comp (ref "U9")
      (value "PC817")
      (footprint "DIP_4")
      (description "OPTOCOUPLER, TRANSISTOR, 4PIN")
      (fields (field (name "MANF") "SHARP"))
      (libsource (lib "optocoupler") (part "OPTC_TR4P_PC817"))
    )
    (comp (ref "U10")
      (value "PC817")
      (footprint "DIP_4")
      (description "OPTOCOUPLER, TRANSISTOR, 4PIN")
      (fields (field (name "MANF") "SHARP"))
      (libsource (lib "optocoupler") (part "OPTC_TR4P_PC817"))
    )
    (comp (ref "U11")
      (value "PC817")
      (footprint "DIP_4")
      (description "OPTOCOUPLER, TRANSISTOR, 4PIN")
      (fields (field (name "MANF") "SHARP"))
      (libsource (lib "optocoupler") (part "OPTC_TR4P_PC817"))
    )
    (comp (ref "U12")
      (value "PC817")
      (footprint "DIP_4")
      (description "OPTOCOUPLER, TRANSISTOR, 4PIN")
      (fields (field (name "MANF") "SHARP"))
      (libsource (lib "optocoupler") (part "OPTC_TR4P_PC817"))
    )
    (comp (ref "U13")
      (value "PC817")
      (footprint "DIP_4")
      (description "OPTOCOUPLER, TRANSISTOR, 4PIN")
      (fields (field (name "MANF") "SHARP"))
      (libsource (lib "optocoupler") (part "OPTC_TR4P_PC817"))
    )
    (comp (ref "U14")
      (value "PC817")
      (footprint "DIP_4")
      (description "OPTOCOUPLER, TRANSISTOR, 4PIN")
      (fields (field (name "MANF") "SHARP"))
      (libsource (lib "optocoupler") (part "OPTC_TR4P_PC817"))
    )
    (comp (ref "U15")
      (value "PC817")
      (footprint "DIP_4")
      (description "OPTOCOUPLER, TRANSISTOR, 4PIN")
      (fields (field (name "MANF") "SHARP"))
      (libsource (lib "optocoupler") (part "OPTC_TR4P_PC817"))
    )
    (comp (ref "U16")
      (value "PC817")
      (footprint "DIP_4")
      (description "OPTOCOUPLER, TRANSISTOR, 4PIN")
      (fields (field (name "MANF") "SHARP"))
      (libsource (lib "optocoupler") (part "OPTC_TR4P_PC817"))
    )
    (comp (ref "U17")
      (value "PC817")
      (footprint "DIP_4")
      (description "OPTOCOUPLER, TRANSISTOR, 4PIN")
      (fields (field (name "MANF") "SHARP"))
      (libsource (lib "optocoupler") (part "OPTC_TR4P_PC817"))
    )
    (comp (ref "U18")
      (value "PC817")
      (footprint "DIP_4")
      (description "OPTOCOUPLER, TRANSISTOR, 4PIN")
      (fields (field (name "MANF") "SHARP"))
      (libsource (lib "optocoupler") (part "OPTC_TR4P_PC817"))
    )
    (comp (ref "U19")
      (value "LD1117-3.3")
      (footprint "SOT223_4")
      (description "REG, Linear, LDO1V, 0.8A, SOT-223")
      (fields
        (field (name "MANF_P#") "LD1117, LM1117, AMS1117, TLV1117, REG1117, NCP1117, LT1117, SPX1117")
        (field (name "MANF") "TI, ON, ST")
      )
      (libsource (lib "pwr_reg_linear_1117") (part "VREG_1117_SOT223"))
    )
    (comp (ref "U20")
      (value "ESP-01")
      (footprint "ESP8266_ESP01")
      (description "ESP8266 ESP-01 WiFi Module")
      (libsource (lib "module_wifi") (part "ESP8266_ESP-01"))
    )
  )
  (nets
    (net (code "1") (name "/IN220vacPUT01") (class "Default")
      (node (ref "J1") (pin "2") (pinfunction "2_2") (pintype "passive"))
      (node (ref "R") (pin "1") (pinfunction "1_1") (pintype "passive"))
    )
    (net (code "2") (name "/IN220vacPUT1N") (class "Default")
      (node (ref "J1") (pin "1") (pinfunction "1_1") (pintype "passive"))
      (node (ref "U1") (pin "2") (pinfunction "K_2") (pintype "passive"))
      (node (ref "U2") (pin "2") (pinfunction "K_2") (pintype "passive"))
      (node (ref "U3") (pin "2") (pinfunction "K_2") (pintype "passive"))
      (node (ref "U4") (pin "2") (pinfunction "K_2") (pintype "passive"))
      (node (ref "U5") (pin "2") (pinfunction "K_2") (pintype "passive"))
      (node (ref "U6") (pin "2") (pinfunction "K_2") (pintype "passive"))
      (node (ref "U7") (pin "2") (pinfunction "K_2") (pintype "passive"))
      (node (ref "U8") (pin "2") (pinfunction "K_2") (pintype "passive"))
      (node (ref "U9") (pin "2") (pinfunction "K_2") (pintype "passive"))
    )
    (net (code "3") (name "/IN220vacPUT02") (class "Default")
      (node (ref "J1") (pin "3") (pinfunction "3_3") (pintype "passive"))
      (node (ref "R1") (pin "1") (pinfunction "1_1") (pintype "passive"))
    )
    (net (code "4") (name "/IN220vacPUT2N") (class "Default")
      (node (ref "J5") (pin "1") (pinfunction "1_1") (pintype "passive"))
      (node (ref "U10") (pin "2") (pinfunction "K_2") (pintype "passive"))
      (node (ref "U11") (pin "2") (pinfunction "K_2") (pintype "passive"))
      (node (ref "U12") (pin "2") (pinfunction "K_2") (pintype "passive"))
      (node (ref "U13") (pin "2") (pinfunction "K_2") (pintype "passive"))
      (node (ref "U14") (pin "2") (pinfunction "K_2") (pintype "passive"))
      (node (ref "U15") (pin "2") (pinfunction "K_2") (pintype "passive"))
      (node (ref "U16") (pin "2") (pinfunction "K_2") (pintype "passive"))
      (node (ref "U17") (pin "2") (pinfunction "K_2") (pintype "passive"))
      (node (ref "U18") (pin "2") (pinfunction "K_2") (pintype "passive"))
    )
    (net (code "5") (name "/IN220vacPUT03") (class "Default")
      (node (ref "J1") (pin "4") (pinfunction "4_4") (pintype "passive"))
      (node (ref "R20") (pin "1") (pinfunction "1_1") (pintype "passive"))
    )
    (net (code "6") (name "/IN220vacPUT04") (class "Default")
      (node (ref "J1") (pin "5") (pinfunction "5_5") (pintype "passive"))
      (node (ref "R21") (pin "1") (pinfunction "1_1") (pintype "passive"))
    )
    (net (code "7") (name "/IN220vacPUT05") (class "Default")
      (node (ref "J1") (pin "6") (pinfunction "6_6") (pintype "passive"))
      (node (ref "R22") (pin "1") (pinfunction "1_1") (pintype "passive"))
    )
    (net (code "8") (name "/IN220vacPUT06") (class "Default")
      (node (ref "J1") (pin "7") (pinfunction "7_7") (pintype "passive"))
      (node (ref "R23") (pin "1") (pinfunction "1_1") (pintype "passive"))
    )
    (net (code "9") (name "/IN220vacPUT07") (class "Default")
      (node (ref "J1") (pin "8") (pinfunction "8_8") (pintype "passive"))
      (node (ref "R29") (pin "1") (pinfunction "1_1") (pintype "passive"))
    )
    (net (code "10") (name "/IN220vacPUT08") (class "Default")
      (node (ref "J1") (pin "9") (pinfunction "9_9") (pintype "passive"))
      (node (ref "R30") (pin "1") (pinfunction "1_1") (pintype "passive"))
    )
    (net (code "11") (name "/IN220vacPUT09") (class "Default")
      (node (ref "J1") (pin "10") (pinfunction "10_10") (pintype "passive"))
      (node (ref "R31") (pin "1") (pinfunction "1_1") (pintype "passive"))
    )
    (net (code "12") (name "/IN220vacPUT10") (class "Default")
      (node (ref "J5") (pin "2") (pinfunction "2_2") (pintype "passive"))
      (node (ref "R32") (pin "1") (pinfunction "1_1") (pintype "passive"))
    )
    (net (code "13") (name "/IN220vacPUT11") (class "Default")
      (node (ref "J5") (pin "3") (pinfunction "3_3") (pintype "passive"))
      (node (ref "R33") (pin "1") (pinfunction "1_1") (pintype "passive"))
    )
    (net (code "14") (name "/IN220vacPUT12") (class "Default")
      (node (ref "J5") (pin "4") (pinfunction "4_4") (pintype "passive"))
      (node (ref "R39") (pin "1") (pinfunction "1_1") (pintype "passive"))
    )
    (net (code "15") (name "/IN220vacPUT13") (class "Default")
      (node (ref "J5") (pin "5") (pinfunction "5_5") (pintype "passive"))
      (node (ref "R40") (pin "1") (pinfunction "1_1") (pintype "passive"))
    )
    (net (code "16") (name "/IN220vacPUT14") (class "Default")
      (node (ref "J5") (pin "6") (pinfunction "6_6") (pintype "passive"))
      (node (ref "R41") (pin "1") (pinfunction "1_1") (pintype "passive"))
    )
    (net (code "17") (name "/IN220vacPUT15") (class "Default")
      (node (ref "J5") (pin "7") (pinfunction "7_7") (pintype "passive"))
      (node (ref "R42") (pin "1") (pinfunction "1_1") (pintype "passive"))
    )
    (net (code "18") (name "/IN220vacPUT16") (class "Default")
      (node (ref "J5") (pin "8") (pinfunction "8_8") (pintype "passive"))
      (node (ref "R47") (pin "1") (pinfunction "1_1") (pintype "passive"))
    )
    (net (code "19") (name "/IN220vacPUT17") (class "Default")
      (node (ref "J5") (pin "9") (pinfunction "9_9") (pintype "passive"))
      (node (ref "R48") (pin "1") (pinfunction "1_1") (pintype "passive"))
    )
    (net (code "20") (name "/IN220vacPUT18") (class "Default")
      (node (ref "J5") (pin "10") (pinfunction "10_10") (pintype "passive"))
      (node (ref "R49") (pin "1") (pinfunction "1_1") (pintype "passive"))
    )
    (net (code "21") (name "/INPUT-flag01") (class "Default")
      (node (ref "J7") (pin "10") (pinfunction "10_10") (pintype "passive"))
      (node (ref "R24") (pin "2") (pinfunction "2_2") (pintype "passive"))
      (node (ref "U1") (pin "3") (pinfunction "E_3") (pintype "passive"))
    )
    (net (code "22") (name "/INPUT-flag02") (class "Default")
      (node (ref "J8") (pin "11") (pinfunction "11_11") (pintype "passive"))
      (node (ref "R25") (pin "2") (pinfunction "2_2") (pintype "passive"))
      (node (ref "U2") (pin "3") (pinfunction "E_3") (pintype "passive"))
    )
    (net (code "23") (name "/INPUT-flag03") (class "Default")
      (node (ref "J8") (pin "10") (pinfunction "10_10") (pintype "passive"))
      (node (ref "R26") (pin "2") (pinfunction "2_2") (pintype "passive"))
      (node (ref "U3") (pin "3") (pinfunction "E_3") (pintype "passive"))
    )
    (net (code "24") (name "/INPUT-flag04") (class "Default")
      (node (ref "J8") (pin "9") (pinfunction "9_9") (pintype "passive"))
      (node (ref "R27") (pin "2") (pinfunction "2_2") (pintype "passive"))
      (node (ref "U4") (pin "3") (pinfunction "E_3") (pintype "passive"))
    )
    (net (code "25") (name "/INPUT-flag05") (class "Default")
      (node (ref "J8") (pin "8") (pinfunction "8_8") (pintype "passive"))
      (node (ref "R28") (pin "2") (pinfunction "2_2") (pintype "passive"))
      (node (ref "U5") (pin "3") (pinfunction "E_3") (pintype "passive"))
    )
    (net (code "26") (name "/INPUT-flag06") (class "Default")
      (node (ref "J8") (pin "7") (pinfunction "7_7") (pintype "passive"))
      (node (ref "R34") (pin "2") (pinfunction "2_2") (pintype "passive"))
      (node (ref "U6") (pin "3") (pinfunction "E_3") (pintype "passive"))
    )
    (net (code "27") (name "/INPUT-flag07") (class "Default")
      (node (ref "J8") (pin "6") (pinfunction "6_6") (pintype "passive"))
      (node (ref "R35") (pin "2") (pinfunction "2_2") (pintype "passive"))
      (node (ref "U7") (pin "3") (pinfunction "E_3") (pintype "passive"))
    )
    (net (code "28") (name "/INPUT-flag08") (class "Default")
      (node (ref "J8") (pin "5") (pinfunction "5_5") (pintype "passive"))
      (node (ref "R36") (pin "2") (pinfunction "2_2") (pintype "passive"))
      (node (ref "U8") (pin "3") (pinfunction "E_3") (pintype "passive"))
    )
    (net (code "29") (name "/INPUT-flag09") (class "Default")
      (node (ref "J8") (pin "4") (pinfunction "4_4") (pintype "passive"))
      (node (ref "R37") (pin "2") (pinfunction "2_2") (pintype "passive"))
      (node (ref "U9") (pin "3") (pinfunction "E_3") (pintype "passive"))
    )
    (net (code "30") (name "/INPUT-flag10") (class "Default")
      (node (ref "J8") (pin "20") (pinfunction "20_20") (pintype "passive"))
      (node (ref "R38") (pin "2") (pinfunction "2_2") (pintype "passive"))
      (node (ref "U10") (pin "3") (pinfunction "E_3") (pintype "passive"))
    )
    (net (code "31") (name "/INPUT-flag11") (class "Default")
      (node (ref "J8") (pin "19") (pinfunction "19_19") (pintype "passive"))
      (node (ref "R43") (pin "2") (pinfunction "2_2") (pintype "passive"))
      (node (ref "U11") (pin "3") (pinfunction "E_3") (pintype "passive"))
    )
    (net (code "32") (name "/INPUT-flag12") (class "Default")
      (node (ref "J8") (pin "18") (pinfunction "18_18") (pintype "passive"))
      (node (ref "R44") (pin "2") (pinfunction "2_2") (pintype "passive"))
      (node (ref "U12") (pin "3") (pinfunction "E_3") (pintype "passive"))
    )
    (net (code "33") (name "/INPUT-flag13") (class "Default")
      (node (ref "J8") (pin "17") (pinfunction "17_17") (pintype "passive"))
      (node (ref "R45") (pin "2") (pinfunction "2_2") (pintype "passive"))
      (node (ref "U13") (pin "3") (pinfunction "E_3") (pintype "passive"))
    )
    (net (code "34") (name "/INPUT-flag14") (class "Default")
      (node (ref "J8") (pin "16") (pinfunction "16_16") (pintype "passive"))
      (node (ref "R46") (pin "2") (pinfunction "2_2") (pintype "passive"))
      (node (ref "U14") (pin "3") (pinfunction "E_3") (pintype "passive"))
    )
    (net (code "35") (name "/INPUT-flag15") (class "Default")
      (node (ref "J8") (pin "15") (pinfunction "15_15") (pintype "passive"))
      (node (ref "R51") (pin "2") (pinfunction "2_2") (pintype "passive"))
      (node (ref "U15") (pin "3") (pinfunction "E_3") (pintype "passive"))
    )
    (net (code "36") (name "/INPUT-flag16") (class "Default")
      (node (ref "J8") (pin "14") (pinfunction "14_14") (pintype "passive"))
      (node (ref "R52") (pin "2") (pinfunction "2_2") (pintype "passive"))
      (node (ref "U16") (pin "3") (pinfunction "E_3") (pintype "passive"))
    )
    (net (code "37") (name "/INPUT-flag17") (class "Default")
      (node (ref "J8") (pin "13") (pinfunction "13_13") (pintype "passive"))
      (node (ref "R53") (pin "2") (pinfunction "2_2") (pintype "passive"))
      (node (ref "U17") (pin "3") (pinfunction "E_3") (pintype "passive"))
    )
    (net (code "38") (name "/INPUT-flag18") (class "Default")
      (node (ref "J8") (pin "12") (pinfunction "12_12") (pintype "passive"))
      (node (ref "R54") (pin "2") (pinfunction "2_2") (pintype "passive"))
      (node (ref "U18") (pin "3") (pinfunction "E_3") (pintype "passive"))
    )
    (net (code "39") (name "/OUTPUT1") (class "Default")
      (node (ref "J7") (pin "4") (pinfunction "4_4") (pintype "passive"))
      (node (ref "R5") (pin "1") (pinfunction "1_1") (pintype "passive"))
    )
    (net (code "40") (name "/OUTPUT2") (class "Default")
      (node (ref "J7") (pin "5") (pinfunction "5_5") (pintype "passive"))
      (node (ref "R11") (pin "1") (pinfunction "1_1") (pintype "passive"))
    )
    (net (code "41") (name "/OUTPUT3") (class "Default")
      (node (ref "J7") (pin "6") (pinfunction "6_6") (pintype "passive"))
      (node (ref "R17") (pin "1") (pinfunction "1_1") (pintype "passive"))
    )
    (net (code "42") (name "/OUTPUT4") (class "Default")
      (node (ref "J7") (pin "15") (pinfunction "15_15") (pintype "passive"))
      (node (ref "R6") (pin "1") (pinfunction "1_1") (pintype "passive"))
    )
    (net (code "43") (name "/OUTPUT5") (class "Default")
      (node (ref "J7") (pin "9") (pinfunction "9_9") (pintype "passive"))
      (node (ref "R12") (pin "1") (pinfunction "1_1") (pintype "passive"))
    )
    (net (code "44") (name "/OUTPUT6") (class "Default")
      (node (ref "J7") (pin "3") (pinfunction "3_3") (pintype "passive"))
      (node (ref "R18") (pin "1") (pinfunction "1_1") (pintype "passive"))
    )
    (net (code "45") (name "/OUTPUT7") (class "Default")
      (node (ref "J7") (pin "13") (pinfunction "13_13") (pintype "passive"))
      (node (ref "R7") (pin "1") (pinfunction "1_1") (pintype "passive"))
    )
    (net (code "46") (name "/OUTPUT8") (class "Default")
      (node (ref "J7") (pin "14") (pinfunction "14_14") (pintype "passive"))
      (node (ref "R13") (pin "1") (pinfunction "1_1") (pintype "passive"))
    )
    (net (code "47") (name "/OUTPUT9") (class "Default")
      (node (ref "J7") (pin "16") (pinfunction "16_16") (pintype "passive"))
      (node (ref "R19") (pin "1") (pinfunction "1_1") (pintype "passive"))
    )
    (net (code "54") (name "/PA6") (class "Default")
      (node (ref "J7") (pin "11") (pinfunction "11_11") (pintype "passive"))
    )
    (net (code "55") (name "/PA7") (class "Default")
      (node (ref "J7") (pin "12") (pinfunction "12_12") (pintype "passive"))
    )
    (net (code "77") (name "/PC13") (class "Default")
      (node (ref "J7") (pin "2") (pinfunction "2_2") (pintype "passive"))
    )
    (net (code "80") (name "/RESET") (class "Default")
      (node (ref "J7") (pin "17") (pinfunction "17_17") (pintype "passive"))
    )
    (net (code "81") (name "/UART2-rx") (class "Default")
      (node (ref "J7") (pin "8") (pinfunction "8_8") (pintype "passive"))
      (node (ref "U20") (pin "8") (pinfunction "GPIO1_U0TXD_8") (pintype "passive"))
    )
    (net (code "82") (name "/UART2-tx") (class "Default")
      (node (ref "J7") (pin "7") (pinfunction "7_7") (pintype "passive"))
      (node (ref "U20") (pin "1") (pinfunction "GPIO3_U0RXD_1") (pintype "passive"))
    )
    (net (code "83") (name "/VBAT") (class "Default")
      (node (ref "J7") (pin "1") (pinfunction "1_1") (pintype "passive"))
    )
    (net (code "84") (name "/com-Rel1") (class "Default")
      (node (ref "J2") (pin "2") (pinfunction "2_2") (pintype "passive"))
      (node (ref "Rel1") (pin "1") (pinfunction "Com_1") (pintype "power_in"))
    )
    (net (code "85") (name "/com-Rel2") (class "Default")
      (node (ref "J2") (pin "5") (pinfunction "5_5") (pintype "passive"))
      (node (ref "Rel2") (pin "1") (pinfunction "Com_1") (pintype "power_in"))
    )
    (net (code "86") (name "/com-Rel3") (class "Default")
      (node (ref "J2") (pin "8") (pinfunction "8_8") (pintype "passive"))
      (node (ref "Rel3") (pin "1") (pinfunction "Com_1") (pintype "power_in"))
    )
    (net (code "87") (name "/com-Rel4") (class "Default")
      (node (ref "J3") (pin "2") (pinfunction "2_2") (pintype "passive"))
      (node (ref "Rel4") (pin "1") (pinfunction "Com_1") (pintype "power_in"))
    )
    (net (code "88") (name "/com-Rel5") (class "Default")
      (node (ref "J3") (pin "5") (pinfunction "5_5") (pintype "passive"))
      (node (ref "Rel5") (pin "1") (pinfunction "Com_1") (pintype "power_in"))
    )
    (net (code "89") (name "/com-Rel6") (class "Default")
      (node (ref "J3") (pin "8") (pinfunction "8_8") (pintype "passive"))
      (node (ref "Rel6") (pin "1") (pinfunction "Com_1") (pintype "power_in"))
    )
    (net (code "90") (name "/com-Rel7") (class "Default")
      (node (ref "J4") (pin "2") (pinfunction "2_2") (pintype "passive"))
      (node (ref "Rel7") (pin "1") (pinfunction "Com_1") (pintype "power_in"))
    )
    (net (code "91") (name "/com-Rel8") (class "Default")
      (node (ref "J4") (pin "5") (pinfunction "5_5") (pintype "passive"))
      (node (ref "Rel8") (pin "1") (pinfunction "Com_1") (pintype "power_in"))
    )
    (net (code "92") (name "/com-Rel9") (class "Default")
      (node (ref "J4") (pin "8") (pinfunction "8_8") (pintype "passive"))
      (node (ref "Rel9") (pin "1") (pinfunction "Com_1") (pintype "power_in"))
    )
    (net (code "93") (name "/nc-Rel1") (class "Default")
      (node (ref "J2") (pin "1") (pinfunction "1_1") (pintype "passive"))
      (node (ref "Rel1") (pin "4") (pinfunction "NC_4") (pintype "power_in"))
    )
    (net (code "94") (name "/nc-Rel2") (class "Default")
      (node (ref "J2") (pin "4") (pinfunction "4_4") (pintype "passive"))
      (node (ref "Rel2") (pin "4") (pinfunction "NC_4") (pintype "power_in"))
    )
    (net (code "95") (name "/nc-Rel3") (class "Default")
      (node (ref "J2") (pin "7") (pinfunction "7_7") (pintype "passive"))
      (node (ref "Rel3") (pin "4") (pinfunction "NC_4") (pintype "power_in"))
    )
    (net (code "96") (name "/nc-Rel4") (class "Default")
      (node (ref "J3") (pin "1") (pinfunction "1_1") (pintype "passive"))
      (node (ref "Rel4") (pin "4") (pinfunction "NC_4") (pintype "power_in"))
    )
    (net (code "97") (name "/nc-Rel5") (class "Default")
      (node (ref "J3") (pin "4") (pinfunction "4_4") (pintype "passive"))
      (node (ref "Rel5") (pin "4") (pinfunction "NC_4") (pintype "power_in"))
    )
    (net (code "98") (name "/nc-Rel6") (class "Default")
      (node (ref "J3") (pin "7") (pinfunction "7_7") (pintype "passive"))
      (node (ref "Rel6") (pin "4") (pinfunction "NC_4") (pintype "power_in"))
    )
    (net (code "99") (name "/nc-Rel7") (class "Default")
      (node (ref "J4") (pin "1") (pinfunction "1_1") (pintype "passive"))
      (node (ref "Rel7") (pin "4") (pinfunction "NC_4") (pintype "power_in"))
    )
    (net (code "100") (name "/nc-Rel8") (class "Default")
      (node (ref "J4") (pin "4") (pinfunction "4_4") (pintype "passive"))
      (node (ref "Rel8") (pin "4") (pinfunction "NC_4") (pintype "power_in"))
    )
    (net (code "101") (name "/nc-Rel9") (class "Default")
      (node (ref "J4") (pin "7") (pinfunction "7_7") (pintype "passive"))
      (node (ref "Rel9") (pin "4") (pinfunction "NC_4") (pintype "power_in"))
    )
    (net (code "102") (name "/no-Rel1") (class "Default")
      (node (ref "J2") (pin "3") (pinfunction "3_3") (pintype "passive"))
      (node (ref "Rel1") (pin "3") (pinfunction "NO_3") (pintype "power_in"))
    )
    (net (code "103") (name "/no-Rel2") (class "Default")
      (node (ref "J2") (pin "6") (pinfunction "6_6") (pintype "passive"))
      (node (ref "Rel2") (pin "3") (pinfunction "NO_3") (pintype "power_in"))
    )
    (net (code "104") (name "/no-Rel3") (class "Default")
      (node (ref "J2") (pin "9") (pinfunction "9_9") (pintype "passive"))
      (node (ref "Rel3") (pin "3") (pinfunction "NO_3") (pintype "power_in"))
    )
    (net (code "105") (name "/no-Rel4") (class "Default")
      (node (ref "J3") (pin "3") (pinfunction "3_3") (pintype "passive"))
      (node (ref "Rel4") (pin "3") (pinfunction "NO_3") (pintype "power_in"))
    )
    (net (code "106") (name "/no-Rel5") (class "Default")
      (node (ref "J3") (pin "6") (pinfunction "6_6") (pintype "passive"))
      (node (ref "Rel5") (pin "3") (pinfunction "NO_3") (pintype "power_in"))
    )
    (net (code "107") (name "/no-Rel6") (class "Default")
      (node (ref "J3") (pin "9") (pinfunction "9_9") (pintype "passive"))
      (node (ref "Rel6") (pin "3") (pinfunction "NO_3") (pintype "power_in"))
    )
    (net (code "108") (name "/no-Rel7") (class "Default")
      (node (ref "J4") (pin "3") (pinfunction "3_3") (pintype "passive"))
      (node (ref "Rel7") (pin "3") (pinfunction "NO_3") (pintype "power_in"))
    )
    (net (code "109") (name "/no-Rel8") (class "Default")
      (node (ref "J4") (pin "6") (pinfunction "6_6") (pintype "passive"))
      (node (ref "Rel8") (pin "3") (pinfunction "NO_3") (pintype "power_in"))
    )
    (net (code "110") (name "/no-Rel9") (class "Default")
      (node (ref "J4") (pin "9") (pinfunction "9_9") (pintype "passive"))
      (node (ref "Rel9") (pin "3") (pinfunction "NO_3") (pintype "power_in"))
    )
    (net (code "111") (name "3.3V") (class "Default")
      (node (ref "C2") (pin "2") (pinfunction "2_2") (pintype "passive"))
      (node (ref "J7") (pin "18") (pinfunction "18_18") (pintype "passive"))
      (node (ref "J8") (pin "1") (pinfunction "1_1") (pintype "passive"))
      (node (ref "R50") (pin "1") (pinfunction "1_1") (pintype "passive"))
      (node (ref "R55") (pin "1") (pinfunction "1_1") (pintype "passive"))
      (node (ref "R56") (pin "1") (pinfunction "1_1") (pintype "passive"))
      (node (ref "R57") (pin "1") (pinfunction "1_1") (pintype "passive"))
      (node (ref "U1") (pin "4") (pinfunction "C_4") (pintype "passive"))
      (node (ref "U10") (pin "4") (pinfunction "C_4") (pintype "passive"))
      (node (ref "U11") (pin "4") (pinfunction "C_4") (pintype "passive"))
      (node (ref "U12") (pin "4") (pinfunction "C_4") (pintype "passive"))
      (node (ref "U13") (pin "4") (pinfunction "C_4") (pintype "passive"))
      (node (ref "U14") (pin "4") (pinfunction "C_4") (pintype "passive"))
      (node (ref "U15") (pin "4") (pinfunction "C_4") (pintype "passive"))
      (node (ref "U16") (pin "4") (pinfunction "C_4") (pintype "passive"))
      (node (ref "U17") (pin "4") (pinfunction "C_4") (pintype "passive"))
      (node (ref "U18") (pin "4") (pinfunction "C_4") (pintype "passive"))
      (node (ref "U19") (pin "2") (pinfunction "VO_2") (pintype "passive"))
      (node (ref "U19") (pin "4") (pinfunction "VO_4") (pintype "passive"))
      (node (ref "U2") (pin "4") (pinfunction "C_4") (pintype "passive"))
      (node (ref "U20") (pin "2") (pinfunction "VCC_2") (pintype "passive"))
      (node (ref "U3") (pin "4") (pinfunction "C_4") (pintype "passive"))
      (node (ref "U4") (pin "4") (pinfunction "C_4") (pintype "passive"))
      (node (ref "U5") (pin "4") (pinfunction "C_4") (pintype "passive"))
      (node (ref "U6") (pin "4") (pinfunction "C_4") (pintype "passive"))
      (node (ref "U7") (pin "4") (pinfunction "C_4") (pintype "passive"))
      (node (ref "U8") (pin "4") (pinfunction "C_4") (pintype "passive"))
      (node (ref "U9") (pin "4") (pinfunction "C_4") (pintype "passive"))
    )
    (net (code "112") (name "5V") (class "Default")
      (node (ref "J8") (pin "3") (pinfunction "3_3") (pintype "passive"))
    )
    (net (code "113") (name "12V") (class "Default")
      (node (ref "C1") (pin "2") (pinfunction "2_2") (pintype "passive"))
      (node (ref "C3") (pin "1") (pinfunction "1_1") (pintype "passive"))
      (node (ref "D1") (pin "1") (pinfunction "A_1") (pintype "passive"))
      (node (ref "D10") (pin "2") (pinfunction "2_2") (pintype "passive"))
      (node (ref "D11") (pin "2") (pinfunction "2_2") (pintype "passive"))
      (node (ref "D12") (pin "2") (pinfunction "2_2") (pintype "passive"))
      (node (ref "D13") (pin "1") (pinfunction "A_1") (pintype "passive"))
      (node (ref "D14") (pin "1") (pinfunction "A_1") (pintype "passive"))
      (node (ref "D15") (pin "1") (pinfunction "A_1") (pintype "passive"))
      (node (ref "D16") (pin "2") (pinfunction "2_2") (pintype "passive"))
      (node (ref "D17") (pin "2") (pinfunction "2_2") (pintype "passive"))
      (node (ref "D18") (pin "2") (pinfunction "2_2") (pintype "passive"))
      (node (ref "D2") (pin "1") (pinfunction "A_1") (pintype "passive"))
      (node (ref "D3") (pin "1") (pinfunction "A_1") (pintype "passive"))
      (node (ref "D4") (pin "2") (pinfunction "2_2") (pintype "passive"))
      (node (ref "D5") (pin "2") (pinfunction "2_2") (pintype "passive"))
      (node (ref "D6") (pin "2") (pinfunction "2_2") (pintype "passive"))
      (node (ref "D7") (pin "1") (pinfunction "A_1") (pintype "passive"))
      (node (ref "D8") (pin "1") (pinfunction "A_1") (pintype "passive"))
      (node (ref "D9") (pin "1") (pinfunction "A_1") (pintype "passive"))
      (node (ref "DB1") (pin "1") (pinfunction "+DC_1") (pintype "passive"))
      (node (ref "Rel1") (pin "2") (pinfunction "Coli1_2") (pintype "power_in"))
      (node (ref "Rel2") (pin "2") (pinfunction "Coli1_2") (pintype "power_in"))
      (node (ref "Rel3") (pin "2") (pinfunction "Coli1_2") (pintype "power_in"))
      (node (ref "Rel4") (pin "2") (pinfunction "Coli1_2") (pintype "power_in"))
      (node (ref "Rel5") (pin "2") (pinfunction "Coli1_2") (pintype "power_in"))
      (node (ref "Rel6") (pin "2") (pinfunction "Coli1_2") (pintype "power_in"))
      (node (ref "Rel7") (pin "2") (pinfunction "Coli1_2") (pintype "power_in"))
      (node (ref "Rel8") (pin "2") (pinfunction "Coli1_2") (pintype "power_in"))
      (node (ref "Rel9") (pin "2") (pinfunction "Coli1_2") (pintype "power_in"))
      (node (ref "U19") (pin "3") (pinfunction "VIN_3") (pintype "passive"))
    )
    (net (code "114") (name "GND") (class "Default")
      (node (ref "C1") (pin "1") (pinfunction "1_1") (pintype "passive"))
      (node (ref "C2") (pin "1") (pinfunction "1_1") (pintype "passive"))
      (node (ref "C3") (pin "2") (pinfunction "2_2") (pintype "passive"))
      (node (ref "DB1") (pin "3") (pinfunction "-DC_3") (pintype "passive"))
      (node (ref "J6") (pin "2") (pinfunction "2_2") (pintype "passive"))
      (node (ref "J7") (pin "19") (pinfunction "19_19") (pintype "passive"))
      (node (ref "J7") (pin "20") (pinfunction "20_20") (pintype "passive"))
      (node (ref "J8") (pin "2") (pinfunction "2_2") (pintype "passive"))
      (node (ref "Q1") (pin "1") (pinfunction "E_1") (pintype "passive"))
      (node (ref "Q2") (pin "1") (pinfunction "E_1") (pintype "passive"))
      (node (ref "Q3") (pin "1") (pinfunction "E_1") (pintype "passive"))
      (node (ref "Q4") (pin "1") (pinfunction "E_1") (pintype "passive"))
      (node (ref "Q5") (pin "1") (pinfunction "E_1") (pintype "passive"))
      (node (ref "Q6") (pin "1") (pinfunction "E_1") (pintype "passive"))
      (node (ref "Q7") (pin "1") (pinfunction "E_1") (pintype "passive"))
      (node (ref "Q8") (pin "1") (pinfunction "E_1") (pintype "passive"))
      (node (ref "Q9") (pin "1") (pinfunction "E_1") (pintype "passive"))
      (node (ref "R24") (pin "1") (pinfunction "1_1") (pintype "passive"))
      (node (ref "R25") (pin "1") (pinfunction "1_1") (pintype "passive"))
      (node (ref "R26") (pin "1") (pinfunction "1_1") (pintype "passive"))
      (node (ref "R27") (pin "1") (pinfunction "1_1") (pintype "passive"))
      (node (ref "R28") (pin "1") (pinfunction "1_1") (pintype "passive"))
      (node (ref "R34") (pin "1") (pinfunction "1_1") (pintype "passive"))
      (node (ref "R35") (pin "1") (pinfunction "1_1") (pintype "passive"))
      (node (ref "R36") (pin "1") (pinfunction "1_1") (pintype "passive"))
      (node (ref "R37") (pin "1") (pinfunction "1_1") (pintype "passive"))
      (node (ref "R38") (pin "1") (pinfunction "1_1") (pintype "passive"))
      (node (ref "R43") (pin "1") (pinfunction "1_1") (pintype "passive"))
      (node (ref "R44") (pin "1") (pinfunction "1_1") (pintype "passive"))
      (node (ref "R45") (pin "1") (pinfunction "1_1") (pintype "passive"))
      (node (ref "R46") (pin "1") (pinfunction "1_1") (pintype "passive"))
      (node (ref "R51") (pin "1") (pinfunction "1_1") (pintype "passive"))
      (node (ref "R52") (pin "1") (pinfunction "1_1") (pintype "passive"))
      (node (ref "R53") (pin "1") (pinfunction "1_1") (pintype "passive"))
      (node (ref "R54") (pin "1") (pinfunction "1_1") (pintype "passive"))
      (node (ref "U19") (pin "1") (pinfunction "GND_1") (pintype "passive"))
      (node (ref "U20") (pin "7") (pinfunction "GND_7") (pintype "passive"))
    )
    (net (code "115") (name "Net-(D1-K)") (class "Default")
      (node (ref "D1") (pin "2") (pinfunction "K_2") (pintype "passive"))
      (node (ref "R2") (pin "2") (pinfunction "2_2") (pintype "passive"))
    )
    (net (code "116") (name "Net-(D2-K)") (class "Default")
      (node (ref "D2") (pin "2") (pinfunction "K_2") (pintype "passive"))
      (node (ref "R8") (pin "2") (pinfunction "2_2") (pintype "passive"))
    )
    (net (code "117") (name "Net-(D3-K)") (class "Default")
      (node (ref "D3") (pin "2") (pinfunction "K_2") (pintype "passive"))
      (node (ref "R14") (pin "2") (pinfunction "2_2") (pintype "passive"))
    )
    (net (code "118") (name "Net-(D7-K)") (class "Default")
      (node (ref "D7") (pin "2") (pinfunction "K_2") (pintype "passive"))
      (node (ref "R3") (pin "2") (pinfunction "2_2") (pintype "passive"))
    )
    (net (code "119") (name "Net-(D8-K)") (class "Default")
      (node (ref "D8") (pin "2") (pinfunction "K_2") (pintype "passive"))
      (node (ref "R9") (pin "2") (pinfunction "2_2") (pintype "passive"))
    )
    (net (code "120") (name "Net-(D9-K)") (class "Default")
      (node (ref "D9") (pin "2") (pinfunction "K_2") (pintype "passive"))
      (node (ref "R15") (pin "2") (pinfunction "2_2") (pintype "passive"))
    )
    (net (code "121") (name "Net-(D13-K)") (class "Default")
      (node (ref "D13") (pin "2") (pinfunction "K_2") (pintype "passive"))
      (node (ref "R4") (pin "2") (pinfunction "2_2") (pintype "passive"))
    )
    (net (code "122") (name "Net-(D14-K)") (class "Default")
      (node (ref "D14") (pin "2") (pinfunction "K_2") (pintype "passive"))
      (node (ref "R10") (pin "2") (pinfunction "2_2") (pintype "passive"))
    )
    (net (code "123") (name "Net-(D15-K)") (class "Default")
      (node (ref "D15") (pin "2") (pinfunction "K_2") (pintype "passive"))
      (node (ref "R16") (pin "2") (pinfunction "2_2") (pintype "passive"))
    )
    (net (code "124") (name "Net-(D19-Pad1)") (class "Default")
      (node (ref "D19") (pin "1") (pinfunction "1_1") (pintype "passive"))
      (node (ref "R") (pin "2") (pinfunction "2_2") (pintype "passive"))
    )
    (net (code "125") (name "Net-(D20-Pad1)") (class "Default")
      (node (ref "D20") (pin "1") (pinfunction "1_1") (pintype "passive"))
      (node (ref "R1") (pin "2") (pinfunction "2_2") (pintype "passive"))
    )
    (net (code "126") (name "Net-(D21-Pad1)") (class "Default")
      (node (ref "D21") (pin "1") (pinfunction "1_1") (pintype "passive"))
      (node (ref "R20") (pin "2") (pinfunction "2_2") (pintype "passive"))
    )
    (net (code "127") (name "Net-(D22-Pad1)") (class "Default")
      (node (ref "D22") (pin "1") (pinfunction "1_1") (pintype "passive"))
      (node (ref "R21") (pin "2") (pinfunction "2_2") (pintype "passive"))
    )
    (net (code "128") (name "Net-(D23-Pad1)") (class "Default")
      (node (ref "D23") (pin "1") (pinfunction "1_1") (pintype "passive"))
      (node (ref "R22") (pin "2") (pinfunction "2_2") (pintype "passive"))
    )
    (net (code "129") (name "Net-(D24-Pad1)") (class "Default")
      (node (ref "D24") (pin "1") (pinfunction "1_1") (pintype "passive"))
      (node (ref "R23") (pin "2") (pinfunction "2_2") (pintype "passive"))
    )
    (net (code "130") (name "Net-(D25-Pad1)") (class "Default")
      (node (ref "D25") (pin "1") (pinfunction "1_1") (pintype "passive"))
      (node (ref "R29") (pin "2") (pinfunction "2_2") (pintype "passive"))
    )
    (net (code "131") (name "Net-(D26-Pad1)") (class "Default")
      (node (ref "D26") (pin "1") (pinfunction "1_1") (pintype "passive"))
      (node (ref "R30") (pin "2") (pinfunction "2_2") (pintype "passive"))
    )
    (net (code "132") (name "Net-(D27-Pad1)") (class "Default")
      (node (ref "D27") (pin "1") (pinfunction "1_1") (pintype "passive"))
      (node (ref "R31") (pin "2") (pinfunction "2_2") (pintype "passive"))
    )
    (net (code "133") (name "Net-(D28-Pad1)") (class "Default")
      (node (ref "D28") (pin "1") (pinfunction "1_1") (pintype "passive"))
      (node (ref "R32") (pin "2") (pinfunction "2_2") (pintype "passive"))
    )
    (net (code "134") (name "Net-(D29-Pad1)") (class "Default")
      (node (ref "D29") (pin "1") (pinfunction "1_1") (pintype "passive"))
      (node (ref "R33") (pin "2") (pinfunction "2_2") (pintype "passive"))
    )
    (net (code "135") (name "Net-(D30-Pad1)") (class "Default")
      (node (ref "D30") (pin "1") (pinfunction "1_1") (pintype "passive"))
      (node (ref "R39") (pin "2") (pinfunction "2_2") (pintype "passive"))
    )
    (net (code "136") (name "Net-(D31-Pad1)") (class "Default")
      (node (ref "D31") (pin "1") (pinfunction "1_1") (pintype "passive"))
      (node (ref "R40") (pin "2") (pinfunction "2_2") (pintype "passive"))
    )
    (net (code "137") (name "Net-(D32-Pad1)") (class "Default")
      (node (ref "D32") (pin "1") (pinfunction "1_1") (pintype "passive"))
      (node (ref "R41") (pin "2") (pinfunction "2_2") (pintype "passive"))
    )
    (net (code "138") (name "Net-(D33-Pad1)") (class "Default")
      (node (ref "D33") (pin "1") (pinfunction "1_1") (pintype "passive"))
      (node (ref "R42") (pin "2") (pinfunction "2_2") (pintype "passive"))
    )
    (net (code "139") (name "Net-(D34-Pad1)") (class "Default")
      (node (ref "D34") (pin "1") (pinfunction "1_1") (pintype "passive"))
      (node (ref "R47") (pin "2") (pinfunction "2_2") (pintype "passive"))
    )
    (net (code "140") (name "Net-(D35-Pad1)") (class "Default")
      (node (ref "D35") (pin "1") (pinfunction "1_1") (pintype "passive"))
      (node (ref "R48") (pin "2") (pinfunction "2_2") (pintype "passive"))
    )
    (net (code "141") (name "Net-(D36-Pad1)") (class "Default")
      (node (ref "D36") (pin "1") (pinfunction "1_1") (pintype "passive"))
      (node (ref "R49") (pin "2") (pinfunction "2_2") (pintype "passive"))
    )
    (net (code "142") (name "Net-(DB1-AC1)") (class "Default")
      (node (ref "DB1") (pin "2") (pinfunction "AC1_2") (pintype "passive"))
      (node (ref "J6") (pin "3") (pinfunction "3_3") (pintype "passive"))
    )
    (net (code "143") (name "Net-(DB1-AC2)") (class "Default")
      (node (ref "DB1") (pin "4") (pinfunction "AC2_4") (pintype "passive"))
      (node (ref "J6") (pin "1") (pinfunction "1_1") (pintype "passive"))
    )
    (net (code "144") (name "Net-(Q1-B)") (class "Default")
      (node (ref "Q1") (pin "3") (pinfunction "B_3") (pintype "passive"))
      (node (ref "R5") (pin "2") (pinfunction "2_2") (pintype "passive"))
    )
    (net (code "145") (name "Net-(Q1-C)") (class "Default")
      (node (ref "D4") (pin "1") (pinfunction "1_1") (pintype "passive"))
      (node (ref "Q1") (pin "2") (pinfunction "C_2") (pintype "passive"))
      (node (ref "R2") (pin "1") (pinfunction "1_1") (pintype "passive"))
      (node (ref "Rel1") (pin "5") (pinfunction "Coli2_5") (pintype "power_in"))
    )
    (net (code "146") (name "Net-(Q2-B)") (class "Default")
      (node (ref "Q2") (pin "3") (pinfunction "B_3") (pintype "passive"))
      (node (ref "R6") (pin "2") (pinfunction "2_2") (pintype "passive"))
    )
    (net (code "147") (name "Net-(Q2-C)") (class "Default")
      (node (ref "D10") (pin "1") (pinfunction "1_1") (pintype "passive"))
      (node (ref "Q2") (pin "2") (pinfunction "C_2") (pintype "passive"))
      (node (ref "R8") (pin "1") (pinfunction "1_1") (pintype "passive"))
      (node (ref "Rel4") (pin "5") (pinfunction "Coli2_5") (pintype "power_in"))
    )
    (net (code "148") (name "Net-(Q3-B)") (class "Default")
      (node (ref "Q3") (pin "3") (pinfunction "B_3") (pintype "passive"))
      (node (ref "R7") (pin "2") (pinfunction "2_2") (pintype "passive"))
    )
    (net (code "149") (name "Net-(Q3-C)") (class "Default")
      (node (ref "D16") (pin "1") (pinfunction "1_1") (pintype "passive"))
      (node (ref "Q3") (pin "2") (pinfunction "C_2") (pintype "passive"))
      (node (ref "R14") (pin "1") (pinfunction "1_1") (pintype "passive"))
      (node (ref "Rel7") (pin "5") (pinfunction "Coli2_5") (pintype "power_in"))
    )
    (net (code "150") (name "Net-(Q4-B)") (class "Default")
      (node (ref "Q4") (pin "3") (pinfunction "B_3") (pintype "passive"))
      (node (ref "R11") (pin "2") (pinfunction "2_2") (pintype "passive"))
    )
    (net (code "151") (name "Net-(Q4-C)") (class "Default")
      (node (ref "D5") (pin "1") (pinfunction "1_1") (pintype "passive"))
      (node (ref "Q4") (pin "2") (pinfunction "C_2") (pintype "passive"))
      (node (ref "R3") (pin "1") (pinfunction "1_1") (pintype "passive"))
      (node (ref "Rel2") (pin "5") (pinfunction "Coli2_5") (pintype "power_in"))
    )
    (net (code "152") (name "Net-(Q5-B)") (class "Default")
      (node (ref "Q5") (pin "3") (pinfunction "B_3") (pintype "passive"))
      (node (ref "R12") (pin "2") (pinfunction "2_2") (pintype "passive"))
    )
    (net (code "153") (name "Net-(Q5-C)") (class "Default")
      (node (ref "D11") (pin "1") (pinfunction "1_1") (pintype "passive"))
      (node (ref "Q5") (pin "2") (pinfunction "C_2") (pintype "passive"))
      (node (ref "R9") (pin "1") (pinfunction "1_1") (pintype "passive"))
      (node (ref "Rel5") (pin "5") (pinfunction "Coli2_5") (pintype "power_in"))
    )
    (net (code "154") (name "Net-(Q6-B)") (class "Default")
      (node (ref "Q6") (pin "3") (pinfunction "B_3") (pintype "passive"))
      (node (ref "R13") (pin "2") (pinfunction "2_2") (pintype "passive"))
    )
    (net (code "155") (name "Net-(Q6-C)") (class "Default")
      (node (ref "D17") (pin "1") (pinfunction "1_1") (pintype "passive"))
      (node (ref "Q6") (pin "2") (pinfunction "C_2") (pintype "passive"))
      (node (ref "R15") (pin "1") (pinfunction "1_1") (pintype "passive"))
      (node (ref "Rel8") (pin "5") (pinfunction "Coli2_5") (pintype "power_in"))
    )
    (net (code "156") (name "Net-(Q7-B)") (class "Default")
      (node (ref "Q7") (pin "3") (pinfunction "B_3") (pintype "passive"))
      (node (ref "R17") (pin "2") (pinfunction "2_2") (pintype "passive"))
    )
    (net (code "157") (name "Net-(Q7-C)") (class "Default")
      (node (ref "D6") (pin "1") (pinfunction "1_1") (pintype "passive"))
      (node (ref "Q7") (pin "2") (pinfunction "C_2") (pintype "passive"))
      (node (ref "R4") (pin "1") (pinfunction "1_1") (pintype "passive"))
      (node (ref "Rel3") (pin "5") (pinfunction "Coli2_5") (pintype "power_in"))
    )
    (net (code "158") (name "Net-(Q8-B)") (class "Default")
      (node (ref "Q8") (pin "3") (pinfunction "B_3") (pintype "passive"))
      (node (ref "R18") (pin "2") (pinfunction "2_2") (pintype "passive"))
    )
    (net (code "159") (name "Net-(Q8-C)") (class "Default")
      (node (ref "D12") (pin "1") (pinfunction "1_1") (pintype "passive"))
      (node (ref "Q8") (pin "2") (pinfunction "C_2") (pintype "passive"))
      (node (ref "R10") (pin "1") (pinfunction "1_1") (pintype "passive"))
      (node (ref "Rel6") (pin "5") (pinfunction "Coli2_5") (pintype "power_in"))
    )
    (net (code "160") (name "Net-(Q9-B)") (class "Default")
      (node (ref "Q9") (pin "3") (pinfunction "B_3") (pintype "passive"))
      (node (ref "R19") (pin "2") (pinfunction "2_2") (pintype "passive"))
    )
    (net (code "161") (name "Net-(Q9-C)") (class "Default")
      (node (ref "D18") (pin "1") (pinfunction "1_1") (pintype "passive"))
      (node (ref "Q9") (pin "2") (pinfunction "C_2") (pintype "passive"))
      (node (ref "R16") (pin "1") (pinfunction "1_1") (pintype "passive"))
      (node (ref "Rel9") (pin "5") (pinfunction "Coli2_5") (pintype "power_in"))
    )
    (net (code "162") (name "Net-(U1-A)") (class "Default")
      (node (ref "D19") (pin "2") (pinfunction "2_2") (pintype "passive"))
      (node (ref "U1") (pin "1") (pinfunction "A_1") (pintype "passive"))
    )
    (net (code "163") (name "Net-(U2-A)") (class "Default")
      (node (ref "D20") (pin "2") (pinfunction "2_2") (pintype "passive"))
      (node (ref "U2") (pin "1") (pinfunction "A_1") (pintype "passive"))
    )
    (net (code "164") (name "Net-(U3-A)") (class "Default")
      (node (ref "D21") (pin "2") (pinfunction "2_2") (pintype "passive"))
      (node (ref "U3") (pin "1") (pinfunction "A_1") (pintype "passive"))
    )
    (net (code "165") (name "Net-(U4-A)") (class "Default")
      (node (ref "D22") (pin "2") (pinfunction "2_2") (pintype "passive"))
      (node (ref "U4") (pin "1") (pinfunction "A_1") (pintype "passive"))
    )
    (net (code "166") (name "Net-(U5-A)") (class "Default")
      (node (ref "D23") (pin "2") (pinfunction "2_2") (pintype "passive"))
      (node (ref "U5") (pin "1") (pinfunction "A_1") (pintype "passive"))
    )
    (net (code "167") (name "Net-(U6-A)") (class "Default")
      (node (ref "D24") (pin "2") (pinfunction "2_2") (pintype "passive"))
      (node (ref "U6") (pin "1") (pinfunction "A_1") (pintype "passive"))
    )
    (net (code "168") (name "Net-(U7-A)") (class "Default")
      (node (ref "D25") (pin "2") (pinfunction "2_2") (pintype "passive"))
      (node (ref "U7") (pin "1") (pinfunction "A_1") (pintype "passive"))
    )
    (net (code "169") (name "Net-(U8-A)") (class "Default")
      (node (ref "D26") (pin "2") (pinfunction "2_2") (pintype "passive"))
      (node (ref "U8") (pin "1") (pinfunction "A_1") (pintype "passive"))
    )
    (net (code "170") (name "Net-(U9-A)") (class "Default")
      (node (ref "D27") (pin "2") (pinfunction "2_2") (pintype "passive"))
      (node (ref "U9") (pin "1") (pinfunction "A_1") (pintype "passive"))
    )
    (net (code "171") (name "Net-(U10-A)") (class "Default")
      (node (ref "D28") (pin "2") (pinfunction "2_2") (pintype "passive"))
      (node (ref "U10") (pin "1") (pinfunction "A_1") (pintype "passive"))
    )
    (net (code "172") (name "Net-(U11-A)") (class "Default")
      (node (ref "D29") (pin "2") (pinfunction "2_2") (pintype "passive"))
      (node (ref "U11") (pin "1") (pinfunction "A_1") (pintype "passive"))
    )
    (net (code "173") (name "Net-(U12-A)") (class "Default")
      (node (ref "D30") (pin "2") (pinfunction "2_2") (pintype "passive"))
      (node (ref "U12") (pin "1") (pinfunction "A_1") (pintype "passive"))
    )
    (net (code "174") (name "Net-(U13-A)") (class "Default")
      (node (ref "D31") (pin "2") (pinfunction "2_2") (pintype "passive"))
      (node (ref "U13") (pin "1") (pinfunction "A_1") (pintype "passive"))
    )
    (net (code "175") (name "Net-(U14-A)") (class "Default")
      (node (ref "D32") (pin "2") (pinfunction "2_2") (pintype "passive"))
      (node (ref "U14") (pin "1") (pinfunction "A_1") (pintype "passive"))
    )
    (net (code "176") (name "Net-(U15-A)") (class "Default")
      (node (ref "D33") (pin "2") (pinfunction "2_2") (pintype "passive"))
      (node (ref "U15") (pin "1") (pinfunction "A_1") (pintype "passive"))
    )
    (net (code "177") (name "Net-(U16-A)") (class "Default")
      (node (ref "D34") (pin "2") (pinfunction "2_2") (pintype "passive"))
      (node (ref "U16") (pin "1") (pinfunction "A_1") (pintype "passive"))
    )
    (net (code "178") (name "Net-(U17-A)") (class "Default")
      (node (ref "D35") (pin "2") (pinfunction "2_2") (pintype "passive"))
      (node (ref "U17") (pin "1") (pinfunction "A_1") (pintype "passive"))
    )
    (net (code "179") (name "Net-(U18-A)") (class "Default")
      (node (ref "D36") (pin "2") (pinfunction "2_2") (pintype "passive"))
      (node (ref "U18") (pin "1") (pinfunction "A_1") (pintype "passive"))
    )
    (net (code "180") (name "Net-(U20-CHIP_PD)") (class "Default")
      (node (ref "R57") (pin "2") (pinfunction "2_2") (pintype "passive"))
      (node (ref "U20") (pin "6") (pinfunction "CHIP_PD_6") (pintype "passive"))
    )
    (net (code "181") (name "Net-(U20-GPIO0)") (class "Default")
      (node (ref "R56") (pin "2") (pinfunction "2_2") (pintype "passive"))
      (node (ref "U20") (pin "3") (pinfunction "GPIO0_3") (pintype "passive"))
    )
    (net (code "182") (name "Net-(U20-GPIO2_U1TXD)") (class "Default")
      (node (ref "R55") (pin "2") (pinfunction "2_2") (pintype "passive"))
      (node (ref "U20") (pin "5") (pinfunction "GPIO2_U1TXD_5") (pintype "passive"))
    )
    (net (code "183") (name "Net-(U20-RESET#)") (class "Default")
      (node (ref "R50") (pin "2") (pinfunction "2_2") (pintype "passive"))
      (node (ref "U20") (pin "4") (pinfunction "RESET#_4") (pintype "passive"))
    )
  )
)
